# Power.net
KiCad netlist of a schematic drawn in Altium Designer
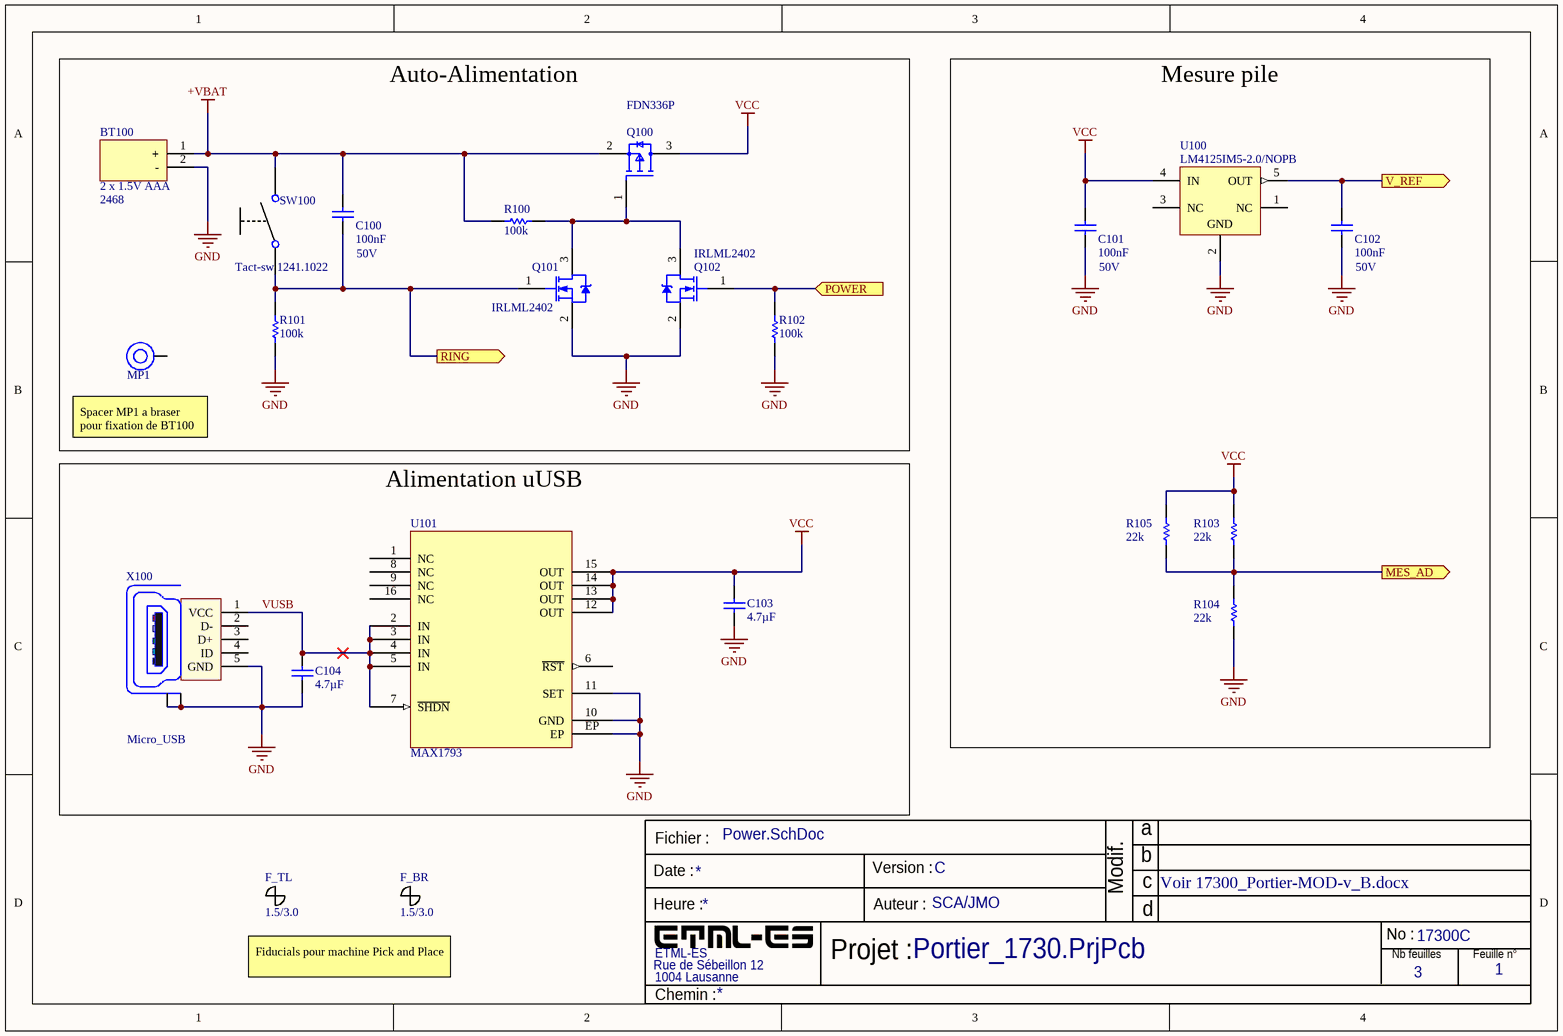
[diagram p0: Power.SchDoc]

(export (version "E")
  (design (tool "Eeschema 10.0.6"))
  (components
    (comp (ref "BT100")
      (value "2 x 1.5V AAA")
      (footprint "2468_3D_Keystone")
      (description "Cylindrical Battery Contacts, Clips, Holders & Springs 2AAA PC MNT HOLDER")
      (fields
        (field (name "MANUFACTURER_PART_NUMBER") "2468")
        (field (name "MOUSER PART NUMBER") "534-2468")
        (field (name "ARROW PART NUMBER") "2468")
      )
      (libsource (lib "Keystone_2468") (part "2468"))
    )
    (comp (ref "C100")
      (value "100nF")
      (footprint "WCAP-CSGP_0805_L2W1.25H0.8_Reflow")
      (description "WCAP-CSGP Multilayer Ceramic Chip Capacitor, General Purpose, size 0805, X7R, 100nF, 50VDC")
      (fields
        (field (name "MANUFACTURER") "Wurth Elektronik")
        (field (name "MANUFACTURER PART NUMBER") "885012207098")
        (field (name "RATED VOLTAGE (DC)") "50V")
      )
      (libsource (lib "Altium_WCAP-CSGP (rev22f)") (part "885012207098"))
    )
    (comp (ref "C101")
      (value "100nF")
      (footprint "WCAP-CSGP_0805_L2W1.25H0.8_Reflow")
      (description "WCAP-CSGP Multilayer Ceramic Chip Capacitor, General Purpose, size 0805, X7R, 100nF, 50VDC")
      (fields
        (field (name "MANUFACTURER") "Wurth Elektronik")
        (field (name "MANUFACTURER PART NUMBER") "885012207098")
        (field (name "RATED VOLTAGE (DC)") "50V")
      )
      (libsource (lib "Altium_WCAP-CSGP (rev22f)") (part "885012207098"))
    )
    (comp (ref "C102")
      (value "100nF")
      (footprint "WCAP-CSGP_0805_L2W1.25H0.8_Reflow")
      (description "WCAP-CSGP Multilayer Ceramic Chip Capacitor, General Purpose, size 0805, X7R, 100nF, 50VDC")
      (fields
        (field (name "MANUFACTURER") "Wurth Elektronik")
        (field (name "MANUFACTURER PART NUMBER") "885012207098")
        (field (name "RATED VOLTAGE (DC)") "50V")
      )
      (libsource (lib "Altium_WCAP-CSGP (rev22f)") (part "885012207098"))
    )
    (comp (ref "C103")
      (value "4.7µF")
      (footprint "WCAP-CSGP_0805_L2W1.25H1.25")
      (description "WCAP-CSGP Multilayer Ceramic Chip Capacitor, General Purpose, size 0805, X7R, 4.7µF, 16VDC")
      (fields (field (name "TOLERANCE") "10%") (field (name "PARTNUMBER") "GRM21BR61C475KA88L"))
      (libsource (lib "Altium_WCAP-CSGP (rev22f)") (part "885012207053"))
    )
    (comp (ref "C104")
      (value "4.7µF")
      (footprint "WCAP-CSGP_0805_L2W1.25H1.25")
      (description "WCAP-CSGP Multilayer Ceramic Chip Capacitor, General Purpose, size 0805, X7R, 4.7µF, 16VDC")
      (fields (field (name "TOLERANCE") "10%") (field (name "PARTNUMBER") "GRM21BR61C475KA88L"))
      (libsource (lib "Altium_WCAP-CSGP (rev22f)") (part "885012207053"))
    )
    (comp (ref "F_BR")
      (value "1.5/3.0")
      (footprint "FID-150-300")
      (description "FID 1.5/3.0")
      (libsource (lib "ETML-ES") (part "FID"))
    )
    (comp (ref "F_TL")
      (value "1.5/3.0")
      (footprint "FID-150-300")
      (description "FID 1.5/3.0")
      (libsource (lib "ETML-ES") (part "FID"))
    )
    (comp (ref "MP1")
      (value "M3 x 3mm")
      (footprint "9774030360")
      (description "WA-SMSI SMT Steel Spacer with internal Thread, OD 6mm, M3 x 3mm")
      (fields
        (field (name "MANUFACTURER PART NUMBER") "9774030360")
        (field (name "MANUFACTURER") "Wurth Elektronik")
      )
      (libsource (lib "Altium_WA-SMSI (rev22a)") (part "9774030360"))
    )
    (comp (ref "Q100")
      (value "FDN336P")
      (footprint "FP-527AG-IPC_A")
      (description "MOSFET P-CH 20V 1.3A SSOT3")
      (libsource (lib "Altium Content Vault") (part "274ba75a4227b453460520a6808ef61"))
    )
    (comp (ref "Q101")
      (value "IRLML2402")
      (footprint "INTR-IRLML2402TRPBF-3_V")
      (description "HEXFET(R) Power MOSFET, N-Channel, 20 V, 1.2 A, 3-Pin SOT-23, RoHS, Tape and Reel")
      (fields
        (field (name "MANUFACTURER") "Infineon Technologies")
        (field (name "PARTNUMBER") "IRLML2402TRBF")
      )
      (libsource (lib "Altium Content Vault") (part "CMP-2000-05155-1"))
    )
    (comp (ref "Q102")
      (value "IRLML2402")
      (footprint "INTR-IRLML2402TRPBF-3_V")
      (description "HEXFET(R) Power MOSFET, N-Channel, 20 V, 1.2 A, 3-Pin SOT-23, RoHS, Tape and Reel")
      (fields
        (field (name "MANUFACTURER") "Infineon Technologies")
        (field (name "PARTNUMBER") "IRLML2402TRBF")
      )
      (libsource (lib "Altium Content Vault") (part "CMP-2000-05155-1"))
    )
    (comp (ref "R100")
      (value "100k")
      (footprint "RESC2013X70X40ML20T20")
      (description "100 kOhms ±1% 0.125W, 1/8W Chip Resistor 0805 (2012 Metric) Automotive AEC-Q200 Thick Film")
      (fields (field (name "PART NUMBER") "ERJ-6ENF1003V") (field (name "MANUFACTURER") "Panasonic"))
      (libsource (lib "Altium Content Vault") (part "RES"))
    )
    (comp (ref "R101")
      (value "100k")
      (footprint "RESC2013X70X40ML20T20")
      (description "100 kOhms ±1% 0.125W, 1/8W Chip Resistor 0805 (2012 Metric) Automotive AEC-Q200 Thick Film")
      (fields (field (name "PART NUMBER") "ERJ-6ENF1003V") (field (name "MANUFACTURER") "Panasonic"))
      (libsource (lib "Altium Content Vault") (part "RES"))
    )
    (comp (ref "R102")
      (value "100k")
      (footprint "RESC2013X70X40ML20T20")
      (description "100 kOhms ±1% 0.125W, 1/8W Chip Resistor 0805 (2012 Metric) Automotive AEC-Q200 Thick Film")
      (fields (field (name "PART NUMBER") "ERJ-6ENF1003V") (field (name "MANUFACTURER") "Panasonic"))
      (libsource (lib "Altium Content Vault") (part "RES"))
    )
    (comp (ref "R103")
      (value "22k")
      (footprint "RESC2013X50X30NL20T20")
      (fields (field (name "MANUFACTURER") "Vishay Dale") (field (name "PART NUMBER") "CRCW080522K0FKEA"))
      (libsource (lib "Altium Content Vault") (part "RES"))
    )
    (comp (ref "R104")
      (value "22k")
      (footprint "RESC2013X50X30NL20T20")
      (fields (field (name "MANUFACTURER") "Vishay Dale") (field (name "PART NUMBER") "CRCW080522K0FKEA"))
      (libsource (lib "Altium Content Vault") (part "RES"))
    )
    (comp (ref "R105")
      (value "22k")
      (footprint "RESC2013X50X30NL20T20")
      (fields (field (name "MANUFACTURER") "Vishay Dale") (field (name "PART NUMBER") "CRCW080522K0FKEA"))
      (libsource (lib "Altium Content Vault") (part "RES"))
    )
    (comp (ref "SW100")
      (value "Tact-sw 1241.1022")
      (footprint "Tact-sw 1241.1022")
      (libsource (lib "Schurter-switches") (part "Tact-sw 1241.1022"))
    )
    (comp (ref "U100")
      (value "LM4125IM5-2.0/NOPB")
      (footprint "DBV0005A_M")
      (description "Precision Micropower Low Dropout Voltage Reference, 5-pin SOT-23, Pb-Free")
      (fields (field (name "MANUFACTURER") "Texas Instruments"))
      (libsource (lib "Altium Content Vault") (part "PM-REF-LM4125-SOT5"))
    )
    (comp (ref "U101")
      (value "MAX1793")
      (footprint "TSOP65P640X110_HS-17N")
      (description "IC REG LINEAR POS ADJ 1A 16TSSOP")
      (fields (field (name "MANUFACTURER") "Maxim Integrated"))
      (libsource (lib "CircuitOUT") (part "MAX1793"))
    )
    (comp (ref "X100")
      (value "Micro_USB")
      (footprint "Micro_USB")
      (description "WR-COM_USB_Micro Type B_Horizontal_SMT")
      (fields
        (field (name "MANUFACTURER") "Würth Elektronik eiSos GmbH")
        (field (name "PARTNUMBER") "629105150521")
      )
      (libsource (lib "CircuitOUT") (part "WR-Communication Connectors 629105150521"))
    )
  )
  (nets
    (net (code "1") (name "+VBAT") (class "Default")
      (node (ref "BT100") (pin "1") (pinfunction "+_1") (pintype "power_in"))
      (node (ref "C100") (pin "2") (pinfunction "2_2") (pintype "passive"))
      (node (ref "Q100") (pin "2") (pinfunction "S_2") (pintype "passive"))
      (node (ref "R100") (pin "2") (pinfunction "2_2") (pintype "passive"))
      (node (ref "SW100") (pin "2") (pinfunction "2_2") (pintype "passive"))
    )
    (net (code "2") (name "/MES_AD") (class "Default")
      (node (ref "R103") (pin "1") (pinfunction "1_1") (pintype "passive"))
      (node (ref "R104") (pin "2") (pinfunction "2_2") (pintype "passive"))
      (node (ref "R105") (pin "1") (pinfunction "1_1") (pintype "passive"))
    )
    (net (code "3") (name "/POWER") (class "Default")
      (node (ref "Q102") (pin "1") (pinfunction "G_1") (pintype "passive"))
      (node (ref "R102") (pin "2") (pinfunction "2_2") (pintype "passive"))
    )
    (net (code "4") (name "/RING") (class "Default")
      (node (ref "C100") (pin "1") (pinfunction "1_1") (pintype "passive"))
      (node (ref "Q101") (pin "1") (pinfunction "G_1") (pintype "passive"))
      (node (ref "R101") (pin "2") (pinfunction "2_2") (pintype "passive"))
      (node (ref "SW100") (pin "1") (pinfunction "1_1") (pintype "passive"))
    )
    (net (code "5") (name "/VUSB") (class "Default")
      (node (ref "C104") (pin "2") (pinfunction "2_2") (pintype "passive"))
      (node (ref "U101") (pin "2") (pinfunction "IN_2") (pintype "passive"))
      (node (ref "U101") (pin "3") (pinfunction "IN_3") (pintype "passive"))
      (node (ref "U101") (pin "4") (pinfunction "IN_4") (pintype "passive"))
      (node (ref "U101") (pin "5") (pinfunction "IN_5") (pintype "passive"))
      (node (ref "U101") (pin "7") (pinfunction "~{SHDN}_7") (pintype "input"))
      (node (ref "X100") (pin "1") (pinfunction "VCC_1") (pintype "passive"))
    )
    (net (code "6") (name "/V_REF") (class "Default")
      (node (ref "C102") (pin "2") (pinfunction "2_2") (pintype "passive"))
      (node (ref "U100") (pin "5") (pinfunction "OUT_5") (pintype "output"))
    )
    (net (code "7") (name "GND") (class "Default")
      (node (ref "BT100") (pin "2") (pinfunction "-_2") (pintype "power_in"))
      (node (ref "C101") (pin "1") (pinfunction "1_1") (pintype "passive"))
      (node (ref "C102") (pin "1") (pinfunction "1_1") (pintype "passive"))
      (node (ref "C103") (pin "1") (pinfunction "1_1") (pintype "passive"))
      (node (ref "C104") (pin "1") (pinfunction "1_1") (pintype "passive"))
      (node (ref "Q101") (pin "2") (pinfunction "S_2") (pintype "passive"))
      (node (ref "Q102") (pin "2") (pinfunction "S_2") (pintype "passive"))
      (node (ref "R101") (pin "1") (pinfunction "1_1") (pintype "passive"))
      (node (ref "R102") (pin "1") (pinfunction "1_1") (pintype "passive"))
      (node (ref "R104") (pin "1") (pinfunction "1_1") (pintype "passive"))
      (node (ref "U100") (pin "2") (pinfunction "GND_2") (pintype "power_in"))
      (node (ref "U101") (pin "10") (pinfunction "GND_10") (pintype "passive"))
      (node (ref "U101") (pin "11") (pinfunction "SET_11") (pintype "passive"))
      (node (ref "U101") (pin "EP") (pinfunction "EP_EP") (pintype "passive"))
      (node (ref "X100") (pin "5") (pinfunction "GND_5") (pintype "passive"))
      (node (ref "X100") (pin "Z1") (pinfunction "Shield_Z1") (pintype "passive"))
      (node (ref "X100") (pin "Z2") (pinfunction "Shield_Z2") (pintype "passive"))
    )
    (net (code "8") (name "Net-(Q100-G)") (class "Default")
      (node (ref "Q100") (pin "1") (pinfunction "G_1") (pintype "passive"))
      (node (ref "Q101") (pin "3") (pinfunction "D_3") (pintype "passive"))
      (node (ref "Q102") (pin "3") (pinfunction "D_3") (pintype "passive"))
      (node (ref "R100") (pin "1") (pinfunction "1_1") (pintype "passive"))
    )
    (net (code "9") (name "VCC") (class "Default")
      (node (ref "C101") (pin "2") (pinfunction "2_2") (pintype "passive"))
      (node (ref "C103") (pin "2") (pinfunction "2_2") (pintype "passive"))
      (node (ref "Q100") (pin "3") (pinfunction "D_3") (pintype "passive"))
      (node (ref "R103") (pin "2") (pinfunction "2_2") (pintype "passive"))
      (node (ref "R105") (pin "2") (pinfunction "2_2") (pintype "passive"))
      (node (ref "U100") (pin "4") (pinfunction "IN_4") (pintype "power_in"))
      (node (ref "U101") (pin "12") (pinfunction "OUT_12") (pintype "passive"))
      (node (ref "U101") (pin "13") (pinfunction "OUT_13") (pintype "passive"))
      (node (ref "U101") (pin "14") (pinfunction "OUT_14") (pintype "passive"))
      (node (ref "U101") (pin "15") (pinfunction "OUT_15") (pintype "passive"))
    )
    (net (code "10") (name "unconnected-(MP1-Pad1)") (class "Default")
      (node (ref "MP1") (pin "1") (pinfunction "1_1") (pintype "passive"))
    )
    (net (code "11") (name "unconnected-(U100-NC-Pad1)") (class "Default")
      (node (ref "U100") (pin "1") (pinfunction "NC_1") (pintype "passive"))
    )
    (net (code "12") (name "unconnected-(U100-NC-Pad3)") (class "Default")
      (node (ref "U100") (pin "3") (pinfunction "NC_3") (pintype "passive"))
    )
    (net (code "13") (name "unconnected-(U101-NC-Pad1)") (class "Default")
      (node (ref "U101") (pin "1") (pinfunction "NC_1") (pintype "passive"))
    )
    (net (code "14") (name "unconnected-(U101-NC-Pad8)") (class "Default")
      (node (ref "U101") (pin "8") (pinfunction "NC_8") (pintype "passive"))
    )
    (net (code "15") (name "unconnected-(U101-NC-Pad9)") (class "Default")
      (node (ref "U101") (pin "9") (pinfunction "NC_9") (pintype "passive"))
    )
    (net (code "16") (name "unconnected-(U101-NC-Pad16)") (class "Default")
      (node (ref "U101") (pin "16") (pinfunction "NC_16") (pintype "passive"))
    )
    (net (code "17") (name "unconnected-(U101-~{RST}-Pad6)") (class "Default")
      (node (ref "U101") (pin "6") (pinfunction "~{RST}_6") (pintype "output"))
    )
    (net (code "18") (name "unconnected-(X100-D+-Pad3)") (class "Default")
      (node (ref "X100") (pin "3") (pinfunction "D+_3") (pintype "passive"))
    )
    (net (code "19") (name "unconnected-(X100-D--Pad2)") (class "Default")
      (node (ref "X100") (pin "2") (pinfunction "D-_2") (pintype "passive"))
    )
    (net (code "20") (name "unconnected-(X100-ID-Pad4)") (class "Default")
      (node (ref "X100") (pin "4") (pinfunction "ID_4") (pintype "passive"))
    )
  )
)
